# stm32f76XV_breakout.net
KiCad netlist of a schematic drawn in EAGLE
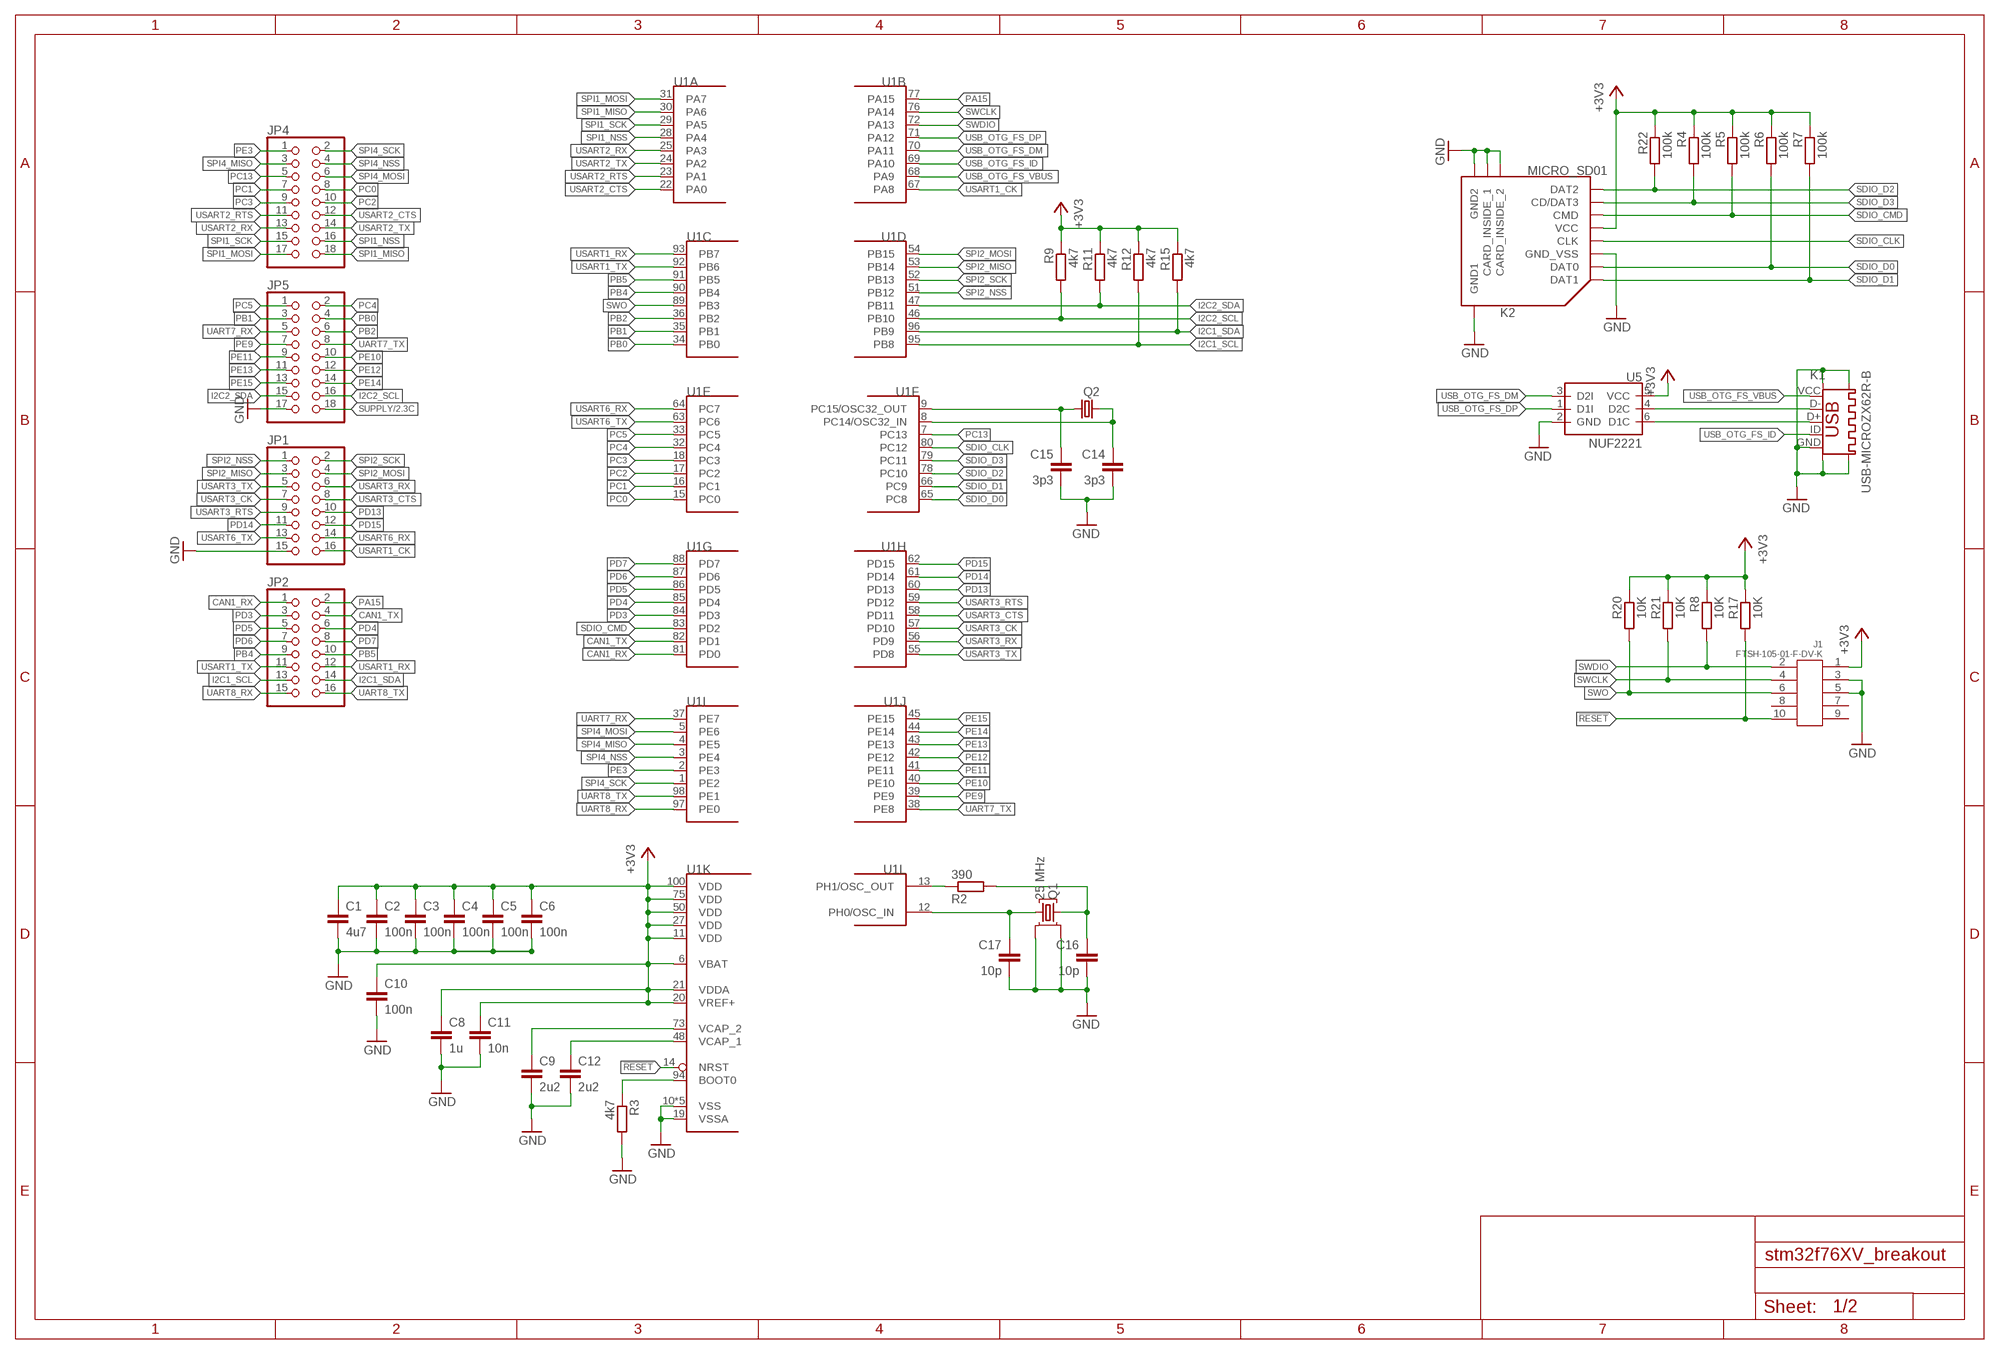
[diagram p0: schematic, sheet 1]
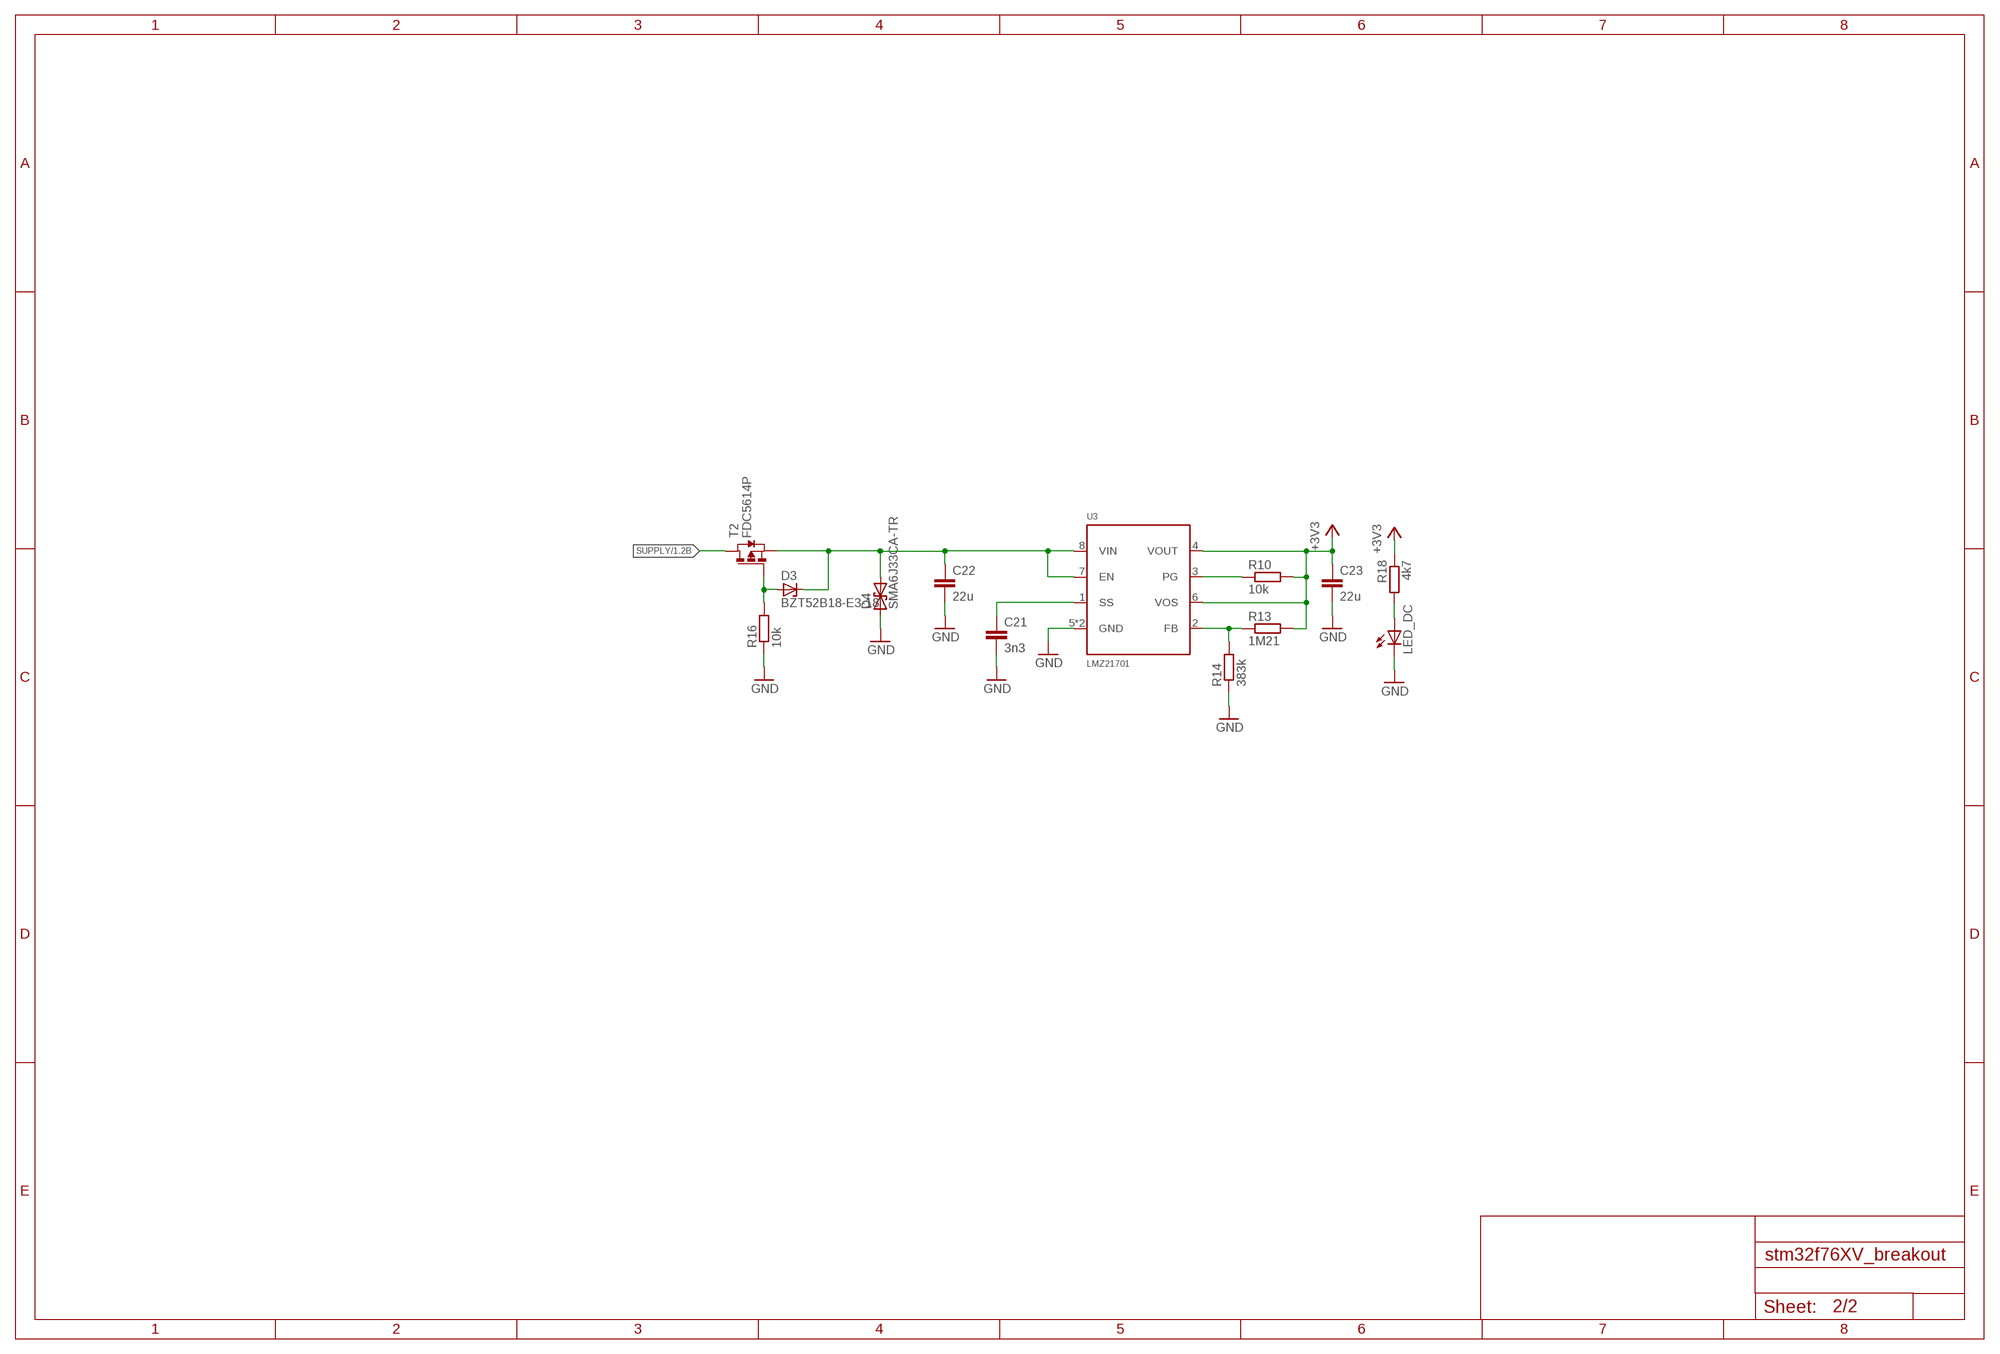
[diagram p1: schematic, sheet 2]

(export (version "E")
  (design (tool "Eeschema 10.0.6"))
  (components
    (comp (ref "C21")
      (value "3n3")
      (footprint "eagle-import:C0603")
      (libsource (lib "eagle-import") (part "C-EUC0603"))
    )
    (comp (ref "C22")
      (value "22u")
      (footprint "eagle-import:C1210")
      (libsource (lib "eagle-import") (part "C-EUC1210"))
    )
    (comp (ref "C23")
      (value "22u")
      (footprint "eagle-import:C1210")
      (libsource (lib "eagle-import") (part "C-EUC1210"))
    )
    (comp (ref "D3")
      (value "BZT52B18-E3-18")
      (footprint "eagle-import:SOD123F")
      (libsource (lib "eagle-import") (part "ZENER_SOD123"))
    )
    (comp (ref "D4")
      (value "SMA6J33CA-TR")
      (footprint "eagle-import:DO214AC")
      (libsource (lib "eagle-import") (part "SMA6J33CA-TR"))
    )
    (comp (ref "LED_DC")
      (value "LEDCHIPLED_0603")
      (footprint "eagle-import:CHIPLED_0603")
      (libsource (lib "eagle-import") (part "LEDCHIPLED_0603"))
    )
    (comp (ref "R10")
      (value "10k")
      (footprint "eagle-import:R0603")
      (libsource (lib "eagle-import") (part "R-EU_R0603"))
    )
    (comp (ref "R13")
      (value "1M21")
      (footprint "eagle-import:R0603")
      (libsource (lib "eagle-import") (part "R-EU_R0603"))
    )
    (comp (ref "R14")
      (value "383k")
      (footprint "eagle-import:R0603")
      (libsource (lib "eagle-import") (part "R-EU_R0603"))
    )
    (comp (ref "R16")
      (value "10k")
      (footprint "eagle-import:R0603")
      (libsource (lib "eagle-import") (part "R-EU_R0603"))
    )
    (comp (ref "R18")
      (value "4k7")
      (footprint "eagle-import:R0603")
      (libsource (lib "eagle-import") (part "R-EU_R0603"))
    )
    (comp (ref "T2")
      (value "FDC5614P")
      (footprint "eagle-import:SSOT6")
      (libsource (lib "eagle-import") (part "FDC5614P"))
    )
    (comp (ref "U3")
      (value "LMZ21701")
      (footprint "eagle-import:SIL0008E")
      (libsource (lib "eagle-import") (part "LMZ21701"))
    )
    (comp (ref "C1")
      (value "4u7")
      (footprint "eagle-import:C0603")
      (libsource (lib "eagle-import") (part "C-EUC0603"))
    )
    (comp (ref "C2")
      (value "100n")
      (footprint "eagle-import:C0603")
      (libsource (lib "eagle-import") (part "C-EUC0603"))
    )
    (comp (ref "C3")
      (value "100n")
      (footprint "eagle-import:C0603")
      (libsource (lib "eagle-import") (part "C-EUC0603"))
    )
    (comp (ref "C4")
      (value "100n")
      (footprint "eagle-import:C0603")
      (libsource (lib "eagle-import") (part "C-EUC0603"))
    )
    (comp (ref "C5")
      (value "100n")
      (footprint "eagle-import:C0603")
      (libsource (lib "eagle-import") (part "C-EUC0603"))
    )
    (comp (ref "C6")
      (value "100n")
      (footprint "eagle-import:C0603")
      (libsource (lib "eagle-import") (part "C-EUC0603"))
    )
    (comp (ref "C8")
      (value "1u")
      (footprint "eagle-import:C0603")
      (libsource (lib "eagle-import") (part "C-EUC0603"))
    )
    (comp (ref "C9")
      (value "2u2")
      (footprint "eagle-import:C0603")
      (libsource (lib "eagle-import") (part "C-EUC0603"))
    )
    (comp (ref "C10")
      (value "100n")
      (footprint "eagle-import:C0603")
      (libsource (lib "eagle-import") (part "C-EUC0603"))
    )
    (comp (ref "C11")
      (value "10n")
      (footprint "eagle-import:C0603")
      (libsource (lib "eagle-import") (part "C-EUC0603"))
    )
    (comp (ref "C12")
      (value "2u2")
      (footprint "eagle-import:C0603")
      (libsource (lib "eagle-import") (part "C-EUC0603"))
    )
    (comp (ref "C14")
      (value "3p3")
      (footprint "eagle-import:C0603")
      (libsource (lib "eagle-import") (part "C-EUC0603"))
    )
    (comp (ref "C15")
      (value "3p3")
      (footprint "eagle-import:C0603")
      (libsource (lib "eagle-import") (part "C-EUC0603"))
    )
    (comp (ref "C16")
      (value "10p")
      (footprint "eagle-import:C0603")
      (libsource (lib "eagle-import") (part "C-EUC0603"))
    )
    (comp (ref "C17")
      (value "10p")
      (footprint "eagle-import:C0603")
      (libsource (lib "eagle-import") (part "C-EUC0603"))
    )
    (comp (ref "J1")
      (value "FTSH-105-01-F-DV-K")
      (footprint "eagle-import:FTSH-105-01-XXX-DV-K")
      (libsource (lib "eagle-import") (part "FTSH-105-01--DV-KF"))
    )
    (comp (ref "JP1")
      (value "PINHD-2X8")
      (footprint "eagle-import:2X08")
      (libsource (lib "eagle-import") (part "PINHD-2X8"))
    )
    (comp (ref "JP2")
      (value "PINHD-2X8")
      (footprint "eagle-import:2X08")
      (libsource (lib "eagle-import") (part "PINHD-2X8"))
    )
    (comp (ref "JP4")
      (value "PINHD-2X9")
      (footprint "eagle-import:2X09")
      (libsource (lib "eagle-import") (part "PINHD-2X9"))
    )
    (comp (ref "JP5")
      (value "PINHD-2X9")
      (footprint "eagle-import:2X09")
      (libsource (lib "eagle-import") (part "PINHD-2X9"))
    )
    (comp (ref "K1")
      (value "USB-MICROZX62R-B")
      (footprint "eagle-import:ZX62R-B")
      (libsource (lib "eagle-import") (part "USB-MICROZX62R-B"))
    )
    (comp (ref "K2")
      (value "MICRO_SD01")
      (footprint "eagle-import:MICRO_SD_473093751")
      (libsource (lib "eagle-import") (part "MICRO_SD01"))
    )
    (comp (ref "Q1")
      (value "25 MHz")
      (footprint "eagle-import:3.2X2.5MM-SMD")
      (libsource (lib "eagle-import") (part "CRYSTAL2M_CX32"))
    )
    (comp (ref "Q2")
      (value "CRYSTAL_ECX-34S")
      (footprint "eagle-import:3.2X1.5MM-SMD")
      (libsource (lib "eagle-import") (part "CRYSTAL_ECX-34S"))
    )
    (comp (ref "R2")
      (value "390")
      (footprint "eagle-import:R0603")
      (libsource (lib "eagle-import") (part "R-EU_R0603"))
    )
    (comp (ref "R3")
      (value "4k7")
      (footprint "eagle-import:R0603")
      (libsource (lib "eagle-import") (part "R-EU_R0603"))
    )
    (comp (ref "R4")
      (value "100k")
      (footprint "eagle-import:R0603")
      (libsource (lib "eagle-import") (part "R-EU_R0603"))
    )
    (comp (ref "R5")
      (value "100k")
      (footprint "eagle-import:R0603")
      (libsource (lib "eagle-import") (part "R-EU_R0603"))
    )
    (comp (ref "R6")
      (value "100k")
      (footprint "eagle-import:R0603")
      (libsource (lib "eagle-import") (part "R-EU_R0603"))
    )
    (comp (ref "R7")
      (value "100k")
      (footprint "eagle-import:R0603")
      (libsource (lib "eagle-import") (part "R-EU_R0603"))
    )
    (comp (ref "R8")
      (value "10K")
      (footprint "eagle-import:R0603")
      (libsource (lib "eagle-import") (part "R-EU_R0603"))
    )
    (comp (ref "R9")
      (value "4k7")
      (footprint "eagle-import:R0603")
      (libsource (lib "eagle-import") (part "R-EU_R0603"))
    )
    (comp (ref "R11")
      (value "4k7")
      (footprint "eagle-import:R0603")
      (libsource (lib "eagle-import") (part "R-EU_R0603"))
    )
    (comp (ref "R12")
      (value "4k7")
      (footprint "eagle-import:R0603")
      (libsource (lib "eagle-import") (part "R-EU_R0603"))
    )
    (comp (ref "R15")
      (value "4k7")
      (footprint "eagle-import:R0603")
      (libsource (lib "eagle-import") (part "R-EU_R0603"))
    )
    (comp (ref "R17")
      (value "10K")
      (footprint "eagle-import:R0603")
      (libsource (lib "eagle-import") (part "R-EU_R0603"))
    )
    (comp (ref "R20")
      (value "10K")
      (footprint "eagle-import:R0603")
      (libsource (lib "eagle-import") (part "R-EU_R0603"))
    )
    (comp (ref "R21")
      (value "10K")
      (footprint "eagle-import:R0603")
      (libsource (lib "eagle-import") (part "R-EU_R0603"))
    )
    (comp (ref "R22")
      (value "100k")
      (footprint "eagle-import:R0603")
      (libsource (lib "eagle-import") (part "R-EU_R0603"))
    )
    (comp (ref "U1")
      (value "STM32F76XVXT")
      (footprint "eagle-import:LQFP-100_14X14MM")
      (libsource (lib "eagle-import") (part "STM32F76XVXT"))
    )
    (comp (ref "U5")
      (value "NUF2221")
      (footprint "eagle-import:SOT363")
      (fields
        (field (name "OC_DIGIKEY") "NUF2221W1T2GOSCT-ND")
        (field (name "ORDER_CODE") "NUF2221W1T2GOSCT-ND")
      )
      (libsource (lib "eagle-import") (part "NUF2221"))
    )
  )
  (nets
    (net (code "1") (name "+3V3") (class "Default")
      (node (ref "C1") (pin "1") (pinfunction "1_1") (pintype "passive"))
      (node (ref "C10") (pin "1") (pinfunction "1_1") (pintype "passive"))
      (node (ref "C11") (pin "1") (pinfunction "1_1") (pintype "passive"))
      (node (ref "C2") (pin "1") (pinfunction "1_1") (pintype "passive"))
      (node (ref "C23") (pin "1") (pinfunction "1_1") (pintype "passive"))
      (node (ref "C3") (pin "1") (pinfunction "1_1") (pintype "passive"))
      (node (ref "C4") (pin "1") (pinfunction "1_1") (pintype "passive"))
      (node (ref "C5") (pin "1") (pinfunction "1_1") (pintype "passive"))
      (node (ref "C6") (pin "1") (pinfunction "1_1") (pintype "passive"))
      (node (ref "C8") (pin "1") (pinfunction "1_1") (pintype "passive"))
      (node (ref "J1") (pin "1") (pinfunction "1_1") (pintype "passive"))
      (node (ref "K2") (pin "VCC") (pinfunction "VCC_VCC") (pintype "bidirectional"))
      (node (ref "R10") (pin "2") (pinfunction "2_2") (pintype "passive"))
      (node (ref "R11") (pin "1") (pinfunction "1_1") (pintype "passive"))
      (node (ref "R12") (pin "1") (pinfunction "1_1") (pintype "passive"))
      (node (ref "R13") (pin "2") (pinfunction "2_2") (pintype "passive"))
      (node (ref "R15") (pin "1") (pinfunction "1_1") (pintype "passive"))
      (node (ref "R17") (pin "1") (pinfunction "1_1") (pintype "passive"))
      (node (ref "R18") (pin "1") (pinfunction "1_1") (pintype "passive"))
      (node (ref "R20") (pin "1") (pinfunction "1_1") (pintype "passive"))
      (node (ref "R21") (pin "1") (pinfunction "1_1") (pintype "passive"))
      (node (ref "R22") (pin "1") (pinfunction "1_1") (pintype "passive"))
      (node (ref "R4") (pin "1") (pinfunction "1_1") (pintype "passive"))
      (node (ref "R5") (pin "1") (pinfunction "1_1") (pintype "passive"))
      (node (ref "R6") (pin "1") (pinfunction "1_1") (pintype "passive"))
      (node (ref "R7") (pin "1") (pinfunction "1_1") (pintype "passive"))
      (node (ref "R8") (pin "1") (pinfunction "1_1") (pintype "passive"))
      (node (ref "R9") (pin "1") (pinfunction "1_1") (pintype "passive"))
      (node (ref "U1") (pin "100") (pinfunction "VDD_100") (pintype "power_in"))
      (node (ref "U1") (pin "11") (pinfunction "VDD_11") (pintype "power_in"))
      (node (ref "U1") (pin "20") (pinfunction "VREF+_20") (pintype "passive"))
      (node (ref "U1") (pin "21") (pinfunction "VDDA_21") (pintype "power_in"))
      (node (ref "U1") (pin "27") (pinfunction "VDD_27") (pintype "power_in"))
      (node (ref "U1") (pin "50") (pinfunction "VDD_50") (pintype "power_in"))
      (node (ref "U1") (pin "6") (pinfunction "VBAT_6") (pintype "power_in"))
      (node (ref "U1") (pin "75") (pinfunction "VDD_75") (pintype "power_in"))
      (node (ref "U3") (pin "4") (pinfunction "VOUT_4") (pintype "passive"))
      (node (ref "U3") (pin "6") (pinfunction "VOS_6") (pintype "input"))
      (node (ref "U5") (pin "5") (pinfunction "VCC_5") (pintype "power_in"))
    )
    (net (code "2") (name "CAN1_RX") (class "Default")
      (node (ref "JP2") (pin "1") (pinfunction "1_1") (pintype "passive"))
      (node (ref "U1") (pin "81") (pinfunction "PD0_81") (pintype "bidirectional"))
    )
    (net (code "3") (name "CAN1_TX") (class "Default")
      (node (ref "JP2") (pin "4") (pinfunction "4_4") (pintype "passive"))
      (node (ref "U1") (pin "82") (pinfunction "PD1_82") (pintype "bidirectional"))
    )
    (net (code "4") (name "GND") (class "Default")
      (node (ref "C1") (pin "2") (pinfunction "2_2") (pintype "passive"))
      (node (ref "C10") (pin "2") (pinfunction "2_2") (pintype "passive"))
      (node (ref "C11") (pin "2") (pinfunction "2_2") (pintype "passive"))
      (node (ref "C12") (pin "2") (pinfunction "2_2") (pintype "passive"))
      (node (ref "C14") (pin "2") (pinfunction "2_2") (pintype "passive"))
      (node (ref "C15") (pin "2") (pinfunction "2_2") (pintype "passive"))
      (node (ref "C16") (pin "2") (pinfunction "2_2") (pintype "passive"))
      (node (ref "C17") (pin "2") (pinfunction "2_2") (pintype "passive"))
      (node (ref "C2") (pin "2") (pinfunction "2_2") (pintype "passive"))
      (node (ref "C21") (pin "2") (pinfunction "2_2") (pintype "passive"))
      (node (ref "C22") (pin "2") (pinfunction "2_2") (pintype "passive"))
      (node (ref "C23") (pin "2") (pinfunction "2_2") (pintype "passive"))
      (node (ref "C3") (pin "2") (pinfunction "2_2") (pintype "passive"))
      (node (ref "C4") (pin "2") (pinfunction "2_2") (pintype "passive"))
      (node (ref "C5") (pin "2") (pinfunction "2_2") (pintype "passive"))
      (node (ref "C6") (pin "2") (pinfunction "2_2") (pintype "passive"))
      (node (ref "C8") (pin "2") (pinfunction "2_2") (pintype "passive"))
      (node (ref "C9") (pin "2") (pinfunction "2_2") (pintype "passive"))
      (node (ref "D4") (pin "A") (pinfunction "1_A") (pintype "passive"))
      (node (ref "J1") (pin "3") (pinfunction "3_3") (pintype "passive"))
      (node (ref "J1") (pin "5") (pinfunction "5_5") (pintype "passive"))
      (node (ref "JP1") (pin "15") (pinfunction "15_15") (pintype "passive"))
      (node (ref "JP5") (pin "17") (pinfunction "17_17") (pintype "passive"))
      (node (ref "K1") (pin "GND") (pinfunction "GND_GND") (pintype "passive"))
      (node (ref "K1") (pin "P$6") (pinfunction "GND3_P$6") (pintype "bidirectional"))
      (node (ref "K1") (pin "P$7") (pinfunction "GND4_P$7") (pintype "bidirectional"))
      (node (ref "K1") (pin "P$8") (pinfunction "GND1_P$8") (pintype "bidirectional"))
      (node (ref "K1") (pin "P$9") (pinfunction "GND2_P$9") (pintype "bidirectional"))
      (node (ref "K2") (pin "C_SW1") (pinfunction "CARD_INSIDE_1_C_SW1") (pintype "bidirectional"))
      (node (ref "K2") (pin "C_SW2") (pinfunction "CARD_INSIDE_2_C_SW2") (pintype "bidirectional"))
      (node (ref "K2") (pin "GND1") (pinfunction "GND1_GND1") (pintype "bidirectional"))
      (node (ref "K2") (pin "GND2") (pinfunction "GND2_GND2") (pintype "bidirectional"))
      (node (ref "K2") (pin "GND_VSS") (pinfunction "GND_VSS_GND_VSS") (pintype "bidirectional"))
      (node (ref "LED_DC") (pin "C") (pinfunction "C_C") (pintype "passive"))
      (node (ref "Q1") (pin "2") (pinfunction "GND1_2") (pintype "power_in"))
      (node (ref "Q1") (pin "4") (pinfunction "GND2_4") (pintype "power_in"))
      (node (ref "R14") (pin "1") (pinfunction "1_1") (pintype "passive"))
      (node (ref "R16") (pin "1") (pinfunction "1_1") (pintype "passive"))
      (node (ref "R3") (pin "2") (pinfunction "2_2") (pintype "passive"))
      (node (ref "U1") (pin "10") (pinfunction "VSS_10") (pintype "power_in"))
      (node (ref "U1") (pin "19") (pinfunction "VSSA_19") (pintype "power_in"))
      (node (ref "U1") (pin "26") (pinfunction "VSS_26") (pintype "power_in"))
      (node (ref "U1") (pin "49") (pinfunction "VSS_49") (pintype "power_in"))
      (node (ref "U1") (pin "74") (pinfunction "VSS_74") (pintype "power_in"))
      (node (ref "U1") (pin "99") (pinfunction "VSS_99") (pintype "power_in"))
      (node (ref "U3") (pin "5") (pinfunction "GND_5") (pintype "power_in"))
      (node (ref "U3") (pin "PAD") (pinfunction "GND_PAD") (pintype "power_in"))
      (node (ref "U5") (pin "2") (pinfunction "GND_2") (pintype "power_in"))
    )
    (net (code "5") (name "I2C1_SCL") (class "Default")
      (node (ref "JP2") (pin "13") (pinfunction "13_13") (pintype "passive"))
      (node (ref "R12") (pin "2") (pinfunction "2_2") (pintype "passive"))
      (node (ref "U1") (pin "95") (pinfunction "PB8_95") (pintype "bidirectional"))
    )
    (net (code "6") (name "I2C1_SDA") (class "Default")
      (node (ref "JP2") (pin "14") (pinfunction "14_14") (pintype "passive"))
      (node (ref "R15") (pin "2") (pinfunction "2_2") (pintype "passive"))
      (node (ref "U1") (pin "96") (pinfunction "PB9_96") (pintype "bidirectional"))
    )
    (net (code "7") (name "I2C2_SCL") (class "Default")
      (node (ref "JP5") (pin "16") (pinfunction "16_16") (pintype "passive"))
      (node (ref "R9") (pin "2") (pinfunction "2_2") (pintype "passive"))
      (node (ref "U1") (pin "46") (pinfunction "PB10_46") (pintype "bidirectional"))
    )
    (net (code "8") (name "I2C2_SDA") (class "Default")
      (node (ref "JP5") (pin "15") (pinfunction "15_15") (pintype "passive"))
      (node (ref "R11") (pin "2") (pinfunction "2_2") (pintype "passive"))
      (node (ref "U1") (pin "47") (pinfunction "PB11_47") (pintype "bidirectional"))
    )
    (net (code "9") (name "Net-(D4-2)") (class "Default")
      (node (ref "C22") (pin "1") (pinfunction "1_1") (pintype "passive"))
      (node (ref "D3") (pin "C") (pinfunction "C_C") (pintype "passive"))
      (node (ref "D4") (pin "C") (pinfunction "2_C") (pintype "passive"))
      (node (ref "T2") (pin "4") (pinfunction "S_4") (pintype "passive"))
      (node (ref "U3") (pin "7") (pinfunction "EN_7") (pintype "input"))
      (node (ref "U3") (pin "8") (pinfunction "VIN_8") (pintype "power_in"))
    )
    (net (code "10") (name "Net-(LED_DC-PadA)") (class "Default")
      (node (ref "LED_DC") (pin "A") (pinfunction "A_A") (pintype "passive"))
      (node (ref "R18") (pin "2") (pinfunction "2_2") (pintype "passive"))
    )
    (net (code "11") (name "Net-(Q1-Q1)") (class "Default")
      (node (ref "C16") (pin "1") (pinfunction "1_1") (pintype "passive"))
      (node (ref "Q1") (pin "1") (pinfunction "Q1_1") (pintype "passive"))
      (node (ref "R2") (pin "2") (pinfunction "2_2") (pintype "passive"))
    )
    (net (code "12") (name "Net-(Q1-Q2)") (class "Default")
      (node (ref "C17") (pin "1") (pinfunction "1_1") (pintype "passive"))
      (node (ref "Q1") (pin "3") (pinfunction "Q2_3") (pintype "passive"))
      (node (ref "U1") (pin "12") (pinfunction "PH0/OSC_IN_12") (pintype "input"))
    )
    (net (code "13") (name "Net-(Q2-1)") (class "Default")
      (node (ref "C14") (pin "1") (pinfunction "1_1") (pintype "passive"))
      (node (ref "Q2") (pin "Q1") (pinfunction "1_Q1") (pintype "passive"))
      (node (ref "U1") (pin "8") (pinfunction "PC14/OSC32_IN_8") (pintype "bidirectional"))
    )
    (net (code "14") (name "Net-(Q2-2)") (class "Default")
      (node (ref "C15") (pin "1") (pinfunction "1_1") (pintype "passive"))
      (node (ref "Q2") (pin "Q2") (pinfunction "2_Q2") (pintype "passive"))
      (node (ref "U1") (pin "9") (pinfunction "PC15/OSC32_OUT_9") (pintype "bidirectional"))
    )
    (net (code "15") (name "Net-(T2-G)") (class "Default")
      (node (ref "D3") (pin "A") (pinfunction "A_A") (pintype "passive"))
      (node (ref "R16") (pin "2") (pinfunction "2_2") (pintype "passive"))
      (node (ref "T2") (pin "3") (pinfunction "G_3") (pintype "passive"))
    )
    (net (code "16") (name "Net-(U1K-BOOT0)") (class "Default")
      (node (ref "R3") (pin "1") (pinfunction "1_1") (pintype "passive"))
      (node (ref "U1") (pin "94") (pinfunction "BOOT0_94") (pintype "bidirectional"))
    )
    (net (code "17") (name "Net-(U1K-VCAP_1)") (class "Default")
      (node (ref "C12") (pin "1") (pinfunction "1_1") (pintype "passive"))
      (node (ref "U1") (pin "48") (pinfunction "VCAP_1_48") (pintype "passive"))
    )
    (net (code "18") (name "Net-(U1K-VCAP_2)") (class "Default")
      (node (ref "C9") (pin "1") (pinfunction "1_1") (pintype "passive"))
      (node (ref "U1") (pin "73") (pinfunction "VCAP_2_73") (pintype "passive"))
    )
    (net (code "19") (name "Net-(U1L-PH1{slash}OSC_OUT)") (class "Default")
      (node (ref "R2") (pin "1") (pinfunction "1_1") (pintype "passive"))
      (node (ref "U1") (pin "13") (pinfunction "PH1/OSC_OUT_13") (pintype "output"))
    )
    (net (code "20") (name "Net-(U3-FB)") (class "Default")
      (node (ref "R13") (pin "1") (pinfunction "1_1") (pintype "passive"))
      (node (ref "R14") (pin "2") (pinfunction "2_2") (pintype "passive"))
      (node (ref "U3") (pin "2") (pinfunction "FB_2") (pintype "input"))
    )
    (net (code "21") (name "Net-(U3-PG)") (class "Default")
      (node (ref "R10") (pin "1") (pinfunction "1_1") (pintype "passive"))
      (node (ref "U3") (pin "3") (pinfunction "PG_3") (pintype "output"))
    )
    (net (code "22") (name "Net-(U3-SS)") (class "Default")
      (node (ref "C21") (pin "1") (pinfunction "1_1") (pintype "passive"))
      (node (ref "U3") (pin "1") (pinfunction "SS_1") (pintype "passive"))
    )
    (net (code "23") (name "Net-(U5-D1C)") (class "Default")
      (node (ref "K1") (pin "D+") (pinfunction "D+_D+") (pintype "passive"))
      (node (ref "U5") (pin "6") (pinfunction "D1C_6") (pintype "bidirectional"))
    )
    (net (code "24") (name "Net-(U5-D2C)") (class "Default")
      (node (ref "K1") (pin "D-") (pinfunction "D-_D-") (pintype "passive"))
      (node (ref "U5") (pin "4") (pinfunction "D2C_4") (pintype "bidirectional"))
    )
    (net (code "25") (name "PA15") (class "Default")
      (node (ref "JP2") (pin "2") (pinfunction "2_2") (pintype "passive"))
      (node (ref "U1") (pin "77") (pinfunction "PA15_77") (pintype "bidirectional"))
    )
    (net (code "26") (name "PB0") (class "Default")
      (node (ref "JP5") (pin "4") (pinfunction "4_4") (pintype "passive"))
      (node (ref "U1") (pin "34") (pinfunction "PB0_34") (pintype "bidirectional"))
    )
    (net (code "27") (name "PB1") (class "Default")
      (node (ref "JP5") (pin "3") (pinfunction "3_3") (pintype "passive"))
      (node (ref "U1") (pin "35") (pinfunction "PB1_35") (pintype "bidirectional"))
    )
    (net (code "28") (name "PB2") (class "Default")
      (node (ref "JP5") (pin "6") (pinfunction "6_6") (pintype "passive"))
      (node (ref "U1") (pin "36") (pinfunction "PB2_36") (pintype "bidirectional"))
    )
    (net (code "29") (name "PB4") (class "Default")
      (node (ref "JP2") (pin "9") (pinfunction "9_9") (pintype "passive"))
      (node (ref "U1") (pin "90") (pinfunction "PB4_90") (pintype "bidirectional"))
    )
    (net (code "30") (name "PB5") (class "Default")
      (node (ref "JP2") (pin "10") (pinfunction "10_10") (pintype "passive"))
      (node (ref "U1") (pin "91") (pinfunction "PB5_91") (pintype "bidirectional"))
    )
    (net (code "31") (name "PC0") (class "Default")
      (node (ref "JP4") (pin "8") (pinfunction "8_8") (pintype "passive"))
      (node (ref "U1") (pin "15") (pinfunction "PC0_15") (pintype "bidirectional"))
    )
    (net (code "32") (name "PC1") (class "Default")
      (node (ref "JP4") (pin "7") (pinfunction "7_7") (pintype "passive"))
      (node (ref "U1") (pin "16") (pinfunction "PC1_16") (pintype "bidirectional"))
    )
    (net (code "33") (name "PC2") (class "Default")
      (node (ref "JP4") (pin "10") (pinfunction "10_10") (pintype "passive"))
      (node (ref "U1") (pin "17") (pinfunction "PC2_17") (pintype "bidirectional"))
    )
    (net (code "34") (name "PC3") (class "Default")
      (node (ref "JP4") (pin "9") (pinfunction "9_9") (pintype "passive"))
      (node (ref "U1") (pin "18") (pinfunction "PC3_18") (pintype "bidirectional"))
    )
    (net (code "35") (name "PC4") (class "Default")
      (node (ref "JP5") (pin "2") (pinfunction "2_2") (pintype "passive"))
      (node (ref "U1") (pin "32") (pinfunction "PC4_32") (pintype "bidirectional"))
    )
    (net (code "36") (name "PC5") (class "Default")
      (node (ref "JP5") (pin "1") (pinfunction "1_1") (pintype "passive"))
      (node (ref "U1") (pin "33") (pinfunction "PC5_33") (pintype "bidirectional"))
    )
    (net (code "37") (name "PC13") (class "Default")
      (node (ref "JP4") (pin "5") (pinfunction "5_5") (pintype "passive"))
      (node (ref "U1") (pin "7") (pinfunction "PC13_7") (pintype "bidirectional"))
    )
    (net (code "38") (name "PD3") (class "Default")
      (node (ref "JP2") (pin "3") (pinfunction "3_3") (pintype "passive"))
      (node (ref "U1") (pin "84") (pinfunction "PD3_84") (pintype "bidirectional"))
    )
    (net (code "39") (name "PD4") (class "Default")
      (node (ref "JP2") (pin "6") (pinfunction "6_6") (pintype "passive"))
      (node (ref "U1") (pin "85") (pinfunction "PD4_85") (pintype "bidirectional"))
    )
    (net (code "40") (name "PD5") (class "Default")
      (node (ref "JP2") (pin "5") (pinfunction "5_5") (pintype "passive"))
      (node (ref "U1") (pin "86") (pinfunction "PD5_86") (pintype "bidirectional"))
    )
    (net (code "41") (name "PD6") (class "Default")
      (node (ref "JP2") (pin "7") (pinfunction "7_7") (pintype "passive"))
      (node (ref "U1") (pin "87") (pinfunction "PD6_87") (pintype "bidirectional"))
    )
    (net (code "42") (name "PD7") (class "Default")
      (node (ref "JP2") (pin "8") (pinfunction "8_8") (pintype "passive"))
      (node (ref "U1") (pin "88") (pinfunction "PD7_88") (pintype "bidirectional"))
    )
    (net (code "43") (name "PD13") (class "Default")
      (node (ref "JP1") (pin "10") (pinfunction "10_10") (pintype "passive"))
      (node (ref "U1") (pin "60") (pinfunction "PD13_60") (pintype "bidirectional"))
    )
    (net (code "44") (name "PD14") (class "Default")
      (node (ref "JP1") (pin "11") (pinfunction "11_11") (pintype "passive"))
      (node (ref "U1") (pin "61") (pinfunction "PD14_61") (pintype "bidirectional"))
    )
    (net (code "45") (name "PD15") (class "Default")
      (node (ref "JP1") (pin "12") (pinfunction "12_12") (pintype "passive"))
      (node (ref "U1") (pin "62") (pinfunction "PD15_62") (pintype "bidirectional"))
    )
    (net (code "46") (name "PE3") (class "Default")
      (node (ref "JP4") (pin "1") (pinfunction "1_1") (pintype "passive"))
      (node (ref "U1") (pin "2") (pinfunction "PE3_2") (pintype "bidirectional"))
    )
    (net (code "47") (name "PE9") (class "Default")
      (node (ref "JP5") (pin "7") (pinfunction "7_7") (pintype "passive"))
      (node (ref "U1") (pin "39") (pinfunction "PE9_39") (pintype "bidirectional"))
    )
    (net (code "48") (name "PE10") (class "Default")
      (node (ref "JP5") (pin "10") (pinfunction "10_10") (pintype "passive"))
      (node (ref "U1") (pin "40") (pinfunction "PE10_40") (pintype "bidirectional"))
    )
    (net (code "49") (name "PE11") (class "Default")
      (node (ref "JP5") (pin "9") (pinfunction "9_9") (pintype "passive"))
      (node (ref "U1") (pin "41") (pinfunction "PE11_41") (pintype "bidirectional"))
    )
    (net (code "50") (name "PE12") (class "Default")
      (node (ref "JP5") (pin "12") (pinfunction "12_12") (pintype "passive"))
      (node (ref "U1") (pin "42") (pinfunction "PE12_42") (pintype "bidirectional"))
    )
    (net (code "51") (name "PE13") (class "Default")
      (node (ref "JP5") (pin "11") (pinfunction "11_11") (pintype "passive"))
      (node (ref "U1") (pin "43") (pinfunction "PE13_43") (pintype "bidirectional"))
    )
    (net (code "52") (name "PE14") (class "Default")
      (node (ref "JP5") (pin "14") (pinfunction "14_14") (pintype "passive"))
      (node (ref "U1") (pin "44") (pinfunction "PE14_44") (pintype "bidirectional"))
    )
    (net (code "53") (name "PE15") (class "Default")
      (node (ref "JP5") (pin "13") (pinfunction "13_13") (pintype "passive"))
      (node (ref "U1") (pin "45") (pinfunction "PE15_45") (pintype "bidirectional"))
    )
    (net (code "54") (name "SDIO_CLK") (class "Default")
      (node (ref "K2") (pin "CLK") (pinfunction "CLK_CLK") (pintype "bidirectional"))
      (node (ref "U1") (pin "80") (pinfunction "PC12_80") (pintype "bidirectional"))
    )
    (net (code "55") (name "SDIO_CMD") (class "Default")
      (node (ref "K2") (pin "CMD") (pinfunction "CMD_CMD") (pintype "bidirectional"))
      (node (ref "R5") (pin "2") (pinfunction "2_2") (pintype "passive"))
      (node (ref "U1") (pin "83") (pinfunction "PD2_83") (pintype "bidirectional"))
    )
    (net (code "56") (name "SDIO_D0") (class "Default")
      (node (ref "K2") (pin "DAT0") (pinfunction "DAT0_DAT0") (pintype "bidirectional"))
      (node (ref "R6") (pin "2") (pinfunction "2_2") (pintype "passive"))
      (node (ref "U1") (pin "65") (pinfunction "PC8_65") (pintype "bidirectional"))
    )
    (net (code "57") (name "SDIO_D1") (class "Default")
      (node (ref "K2") (pin "DAT1") (pinfunction "DAT1_DAT1") (pintype "bidirectional"))
      (node (ref "R7") (pin "2") (pinfunction "2_2") (pintype "passive"))
      (node (ref "U1") (pin "66") (pinfunction "PC9_66") (pintype "bidirectional"))
    )
    (net (code "58") (name "SDIO_D2") (class "Default")
      (node (ref "K2") (pin "DAT2") (pinfunction "DAT2_DAT2") (pintype "bidirectional"))
      (node (ref "R22") (pin "2") (pinfunction "2_2") (pintype "passive"))
      (node (ref "U1") (pin "78") (pinfunction "PC10_78") (pintype "bidirectional"))
    )
    (net (code "59") (name "SDIO_D3") (class "Default")
      (node (ref "K2") (pin "CD/DAT3") (pinfunction "CD/DAT3_CD/DAT3") (pintype "bidirectional"))
      (node (ref "R4") (pin "2") (pinfunction "2_2") (pintype "passive"))
      (node (ref "U1") (pin "79") (pinfunction "PC11_79") (pintype "bidirectional"))
    )
    (net (code "60") (name "SPI1_MISO") (class "Default")
      (node (ref "JP4") (pin "18") (pinfunction "18_18") (pintype "passive"))
      (node (ref "U1") (pin "30") (pinfunction "PA6_30") (pintype "bidirectional"))
    )
    (net (code "61") (name "SPI1_MOSI") (class "Default")
      (node (ref "JP4") (pin "17") (pinfunction "17_17") (pintype "passive"))
      (node (ref "U1") (pin "31") (pinfunction "PA7_31") (pintype "bidirectional"))
    )
    (net (code "62") (name "SPI1_NSS") (class "Default")
      (node (ref "JP4") (pin "16") (pinfunction "16_16") (pintype "passive"))
      (node (ref "U1") (pin "28") (pinfunction "PA4_28") (pintype "bidirectional"))
    )
    (net (code "63") (name "SPI1_SCK") (class "Default")
      (node (ref "JP4") (pin "15") (pinfunction "15_15") (pintype "passive"))
      (node (ref "U1") (pin "29") (pinfunction "PA5_29") (pintype "bidirectional"))
    )
    (net (code "64") (name "SPI2_MISO") (class "Default")
      (node (ref "JP1") (pin "3") (pinfunction "3_3") (pintype "passive"))
      (node (ref "U1") (pin "53") (pinfunction "PB14_53") (pintype "bidirectional"))
    )
    (net (code "65") (name "SPI2_MOSI") (class "Default")
      (node (ref "JP1") (pin "4") (pinfunction "4_4") (pintype "passive"))
      (node (ref "U1") (pin "54") (pinfunction "PB15_54") (pintype "bidirectional"))
    )
    (net (code "66") (name "SPI2_NSS") (class "Default")
      (node (ref "JP1") (pin "1") (pinfunction "1_1") (pintype "passive"))
      (node (ref "U1") (pin "51") (pinfunction "PB12_51") (pintype "bidirectional"))
    )
    (net (code "67") (name "SPI2_SCK") (class "Default")
      (node (ref "JP1") (pin "2") (pinfunction "2_2") (pintype "passive"))
      (node (ref "U1") (pin "52") (pinfunction "PB13_52") (pintype "bidirectional"))
    )
    (net (code "68") (name "SPI4_MISO") (class "Default")
      (node (ref "JP4") (pin "3") (pinfunction "3_3") (pintype "passive"))
      (node (ref "U1") (pin "4") (pinfunction "PE5_4") (pintype "bidirectional"))
    )
    (net (code "69") (name "SPI4_MOSI") (class "Default")
      (node (ref "JP4") (pin "6") (pinfunction "6_6") (pintype "passive"))
      (node (ref "U1") (pin "5") (pinfunction "PE6_5") (pintype "bidirectional"))
    )
    (net (code "70") (name "SPI4_NSS") (class "Default")
      (node (ref "JP4") (pin "4") (pinfunction "4_4") (pintype "passive"))
      (node (ref "U1") (pin "3") (pinfunction "PE4_3") (pintype "bidirectional"))
    )
    (net (code "71") (name "SPI4_SCK") (class "Default")
      (node (ref "JP4") (pin "2") (pinfunction "2_2") (pintype "passive"))
      (node (ref "U1") (pin "1") (pinfunction "PE2_1") (pintype "bidirectional"))
    )
    (net (code "72") (name "SUPPLY") (class "Default")
      (node (ref "JP5") (pin "18") (pinfunction "18_18") (pintype "passive"))
      (node (ref "T2") (pin "1") (pinfunction "D_1") (pintype "passive"))
      (node (ref "T2") (pin "2") (pinfunction "D_2") (pintype "passive"))
      (node (ref "T2") (pin "5") (pinfunction "D_5") (pintype "passive"))
      (node (ref "T2") (pin "6") (pinfunction "D_6") (pintype "passive"))
    )
    (net (code "73") (name "SWCLK") (class "Default")
      (node (ref "J1") (pin "4") (pinfunction "4_4") (pintype "passive"))
      (node (ref "R21") (pin "2") (pinfunction "2_2") (pintype "passive"))
      (node (ref "U1") (pin "76") (pinfunction "PA14_76") (pintype "bidirectional"))
    )
    (net (code "74") (name "SWDIO") (class "Default")
      (node (ref "J1") (pin "2") (pinfunction "2_2") (pintype "passive"))
      (node (ref "R8") (pin "2") (pinfunction "2_2") (pintype "passive"))
      (node (ref "U1") (pin "72") (pinfunction "PA13_72") (pintype "bidirectional"))
    )
    (net (code "75") (name "SWO") (class "Default")
      (node (ref "J1") (pin "6") (pinfunction "6_6") (pintype "passive"))
      (node (ref "R20") (pin "2") (pinfunction "2_2") (pintype "passive"))
      (node (ref "U1") (pin "89") (pinfunction "PB3_89") (pintype "bidirectional"))
    )
    (net (code "76") (name "UART7_RX") (class "Default")
      (node (ref "JP5") (pin "5") (pinfunction "5_5") (pintype "passive"))
      (node (ref "U1") (pin "37") (pinfunction "PE7_37") (pintype "bidirectional"))
    )
    (net (code "77") (name "UART7_TX") (class "Default")
      (node (ref "JP5") (pin "8") (pinfunction "8_8") (pintype "passive"))
      (node (ref "U1") (pin "38") (pinfunction "PE8_38") (pintype "bidirectional"))
    )
    (net (code "78") (name "UART8_RX") (class "Default")
      (node (ref "JP2") (pin "15") (pinfunction "15_15") (pintype "passive"))
      (node (ref "U1") (pin "97") (pinfunction "PE0_97") (pintype "bidirectional"))
    )
    (net (code "79") (name "UART8_TX") (class "Default")
      (node (ref "JP2") (pin "16") (pinfunction "16_16") (pintype "passive"))
      (node (ref "U1") (pin "98") (pinfunction "PE1_98") (pintype "bidirectional"))
    )
    (net (code "80") (name "USART1_CK") (class "Default")
      (node (ref "JP1") (pin "16") (pinfunction "16_16") (pintype "passive"))
      (node (ref "U1") (pin "67") (pinfunction "PA8_67") (pintype "bidirectional"))
    )
    (net (code "81") (name "USART1_RX") (class "Default")
      (node (ref "JP2") (pin "12") (pinfunction "12_12") (pintype "passive"))
      (node (ref "U1") (pin "93") (pinfunction "PB7_93") (pintype "bidirectional"))
    )
    (net (code "82") (name "USART1_TX") (class "Default")
      (node (ref "JP2") (pin "11") (pinfunction "11_11") (pintype "passive"))
      (node (ref "U1") (pin "92") (pinfunction "PB6_92") (pintype "bidirectional"))
    )
    (net (code "83") (name "USART2_CTS") (class "Default")
      (node (ref "JP4") (pin "12") (pinfunction "12_12") (pintype "passive"))
      (node (ref "U1") (pin "22") (pinfunction "PA0_22") (pintype "bidirectional"))
    )
    (net (code "84") (name "USART2_RTS") (class "Default")
      (node (ref "JP4") (pin "11") (pinfunction "11_11") (pintype "passive"))
      (node (ref "U1") (pin "23") (pinfunction "PA1_23") (pintype "bidirectional"))
    )
    (net (code "85") (name "USART2_RX") (class "Default")
      (node (ref "JP4") (pin "13") (pinfunction "13_13") (pintype "passive"))
      (node (ref "U1") (pin "25") (pinfunction "PA3_25") (pintype "bidirectional"))
    )
    (net (code "86") (name "USART2_TX") (class "Default")
      (node (ref "JP4") (pin "14") (pinfunction "14_14") (pintype "passive"))
      (node (ref "U1") (pin "24") (pinfunction "PA2_24") (pintype "bidirectional"))
    )
    (net (code "87") (name "USART3_CK") (class "Default")
      (node (ref "JP1") (pin "7") (pinfunction "7_7") (pintype "passive"))
      (node (ref "U1") (pin "57") (pinfunction "PD10_57") (pintype "bidirectional"))
    )
    (net (code "88") (name "USART3_CTS") (class "Default")
      (node (ref "JP1") (pin "8") (pinfunction "8_8") (pintype "passive"))
      (node (ref "U1") (pin "58") (pinfunction "PD11_58") (pintype "bidirectional"))
    )
    (net (code "89") (name "USART3_RTS") (class "Default")
      (node (ref "JP1") (pin "9") (pinfunction "9_9") (pintype "passive"))
      (node (ref "U1") (pin "59") (pinfunction "PD12_59") (pintype "bidirectional"))
    )
    (net (code "90") (name "USART3_RX") (class "Default")
      (node (ref "JP1") (pin "6") (pinfunction "6_6") (pintype "passive"))
      (node (ref "U1") (pin "56") (pinfunction "PD9_56") (pintype "bidirectional"))
    )
    (net (code "91") (name "USART3_TX") (class "Default")
      (node (ref "JP1") (pin "5") (pinfunction "5_5") (pintype "passive"))
      (node (ref "U1") (pin "55") (pinfunction "PD8_55") (pintype "bidirectional"))
    )
    (net (code "92") (name "USART6_RX") (class "Default")
      (node (ref "JP1") (pin "14") (pinfunction "14_14") (pintype "passive"))
      (node (ref "U1") (pin "64") (pinfunction "PC7_64") (pintype "bidirectional"))
    )
    (net (code "93") (name "USART6_TX") (class "Default")
      (node (ref "JP1") (pin "13") (pinfunction "13_13") (pintype "passive"))
      (node (ref "U1") (pin "63") (pinfunction "PC6_63") (pintype "bidirectional"))
    )
    (net (code "94") (name "USB_OTG_FS_DM") (class "Default")
      (node (ref "U1") (pin "70") (pinfunction "PA11_70") (pintype "bidirectional"))
      (node (ref "U5") (pin "3") (pinfunction "D2I_3") (pintype "bidirectional"))
    )
    (net (code "95") (name "USB_OTG_FS_DP") (class "Default")
      (node (ref "U1") (pin "71") (pinfunction "PA12_71") (pintype "bidirectional"))
      (node (ref "U5") (pin "1") (pinfunction "D1I_1") (pintype "bidirectional"))
    )
    (net (code "96") (name "USB_OTG_FS_ID") (class "Default")
      (node (ref "K1") (pin "ID") (pinfunction "ID_ID") (pintype "passive"))
      (node (ref "U1") (pin "69") (pinfunction "PA10_69") (pintype "bidirectional"))
    )
    (net (code "97") (name "USB_OTG_FS_VBUS") (class "Default")
      (node (ref "K1") (pin "VCC") (pinfunction "VCC_VCC") (pintype "passive"))
      (node (ref "U1") (pin "68") (pinfunction "PA9_68") (pintype "bidirectional"))
    )
    (net (code "98") (name "unconnected-(J1-Pad7)") (class "Default")
      (node (ref "J1") (pin "7") (pinfunction "7_7") (pintype "passive"))
    )
    (net (code "99") (name "unconnected-(J1-Pad8)") (class "Default")
      (node (ref "J1") (pin "8") (pinfunction "8_8") (pintype "passive"))
    )
    (net (code "100") (name "unconnected-(J1-Pad9)") (class "Default")
      (node (ref "J1") (pin "9") (pinfunction "9_9") (pintype "passive"))
    )
    (net (code "101") (name "~{RESET}") (class "Default")
      (node (ref "J1") (pin "10") (pinfunction "10_10") (pintype "passive"))
      (node (ref "R17") (pin "2") (pinfunction "2_2") (pintype "passive"))
      (node (ref "U1") (pin "14") (pinfunction "NRST_14") (pintype "input"))
    )
  )
)
